# SquidPage.net
KiCad netlist of a schematic drawn in Altium Designer
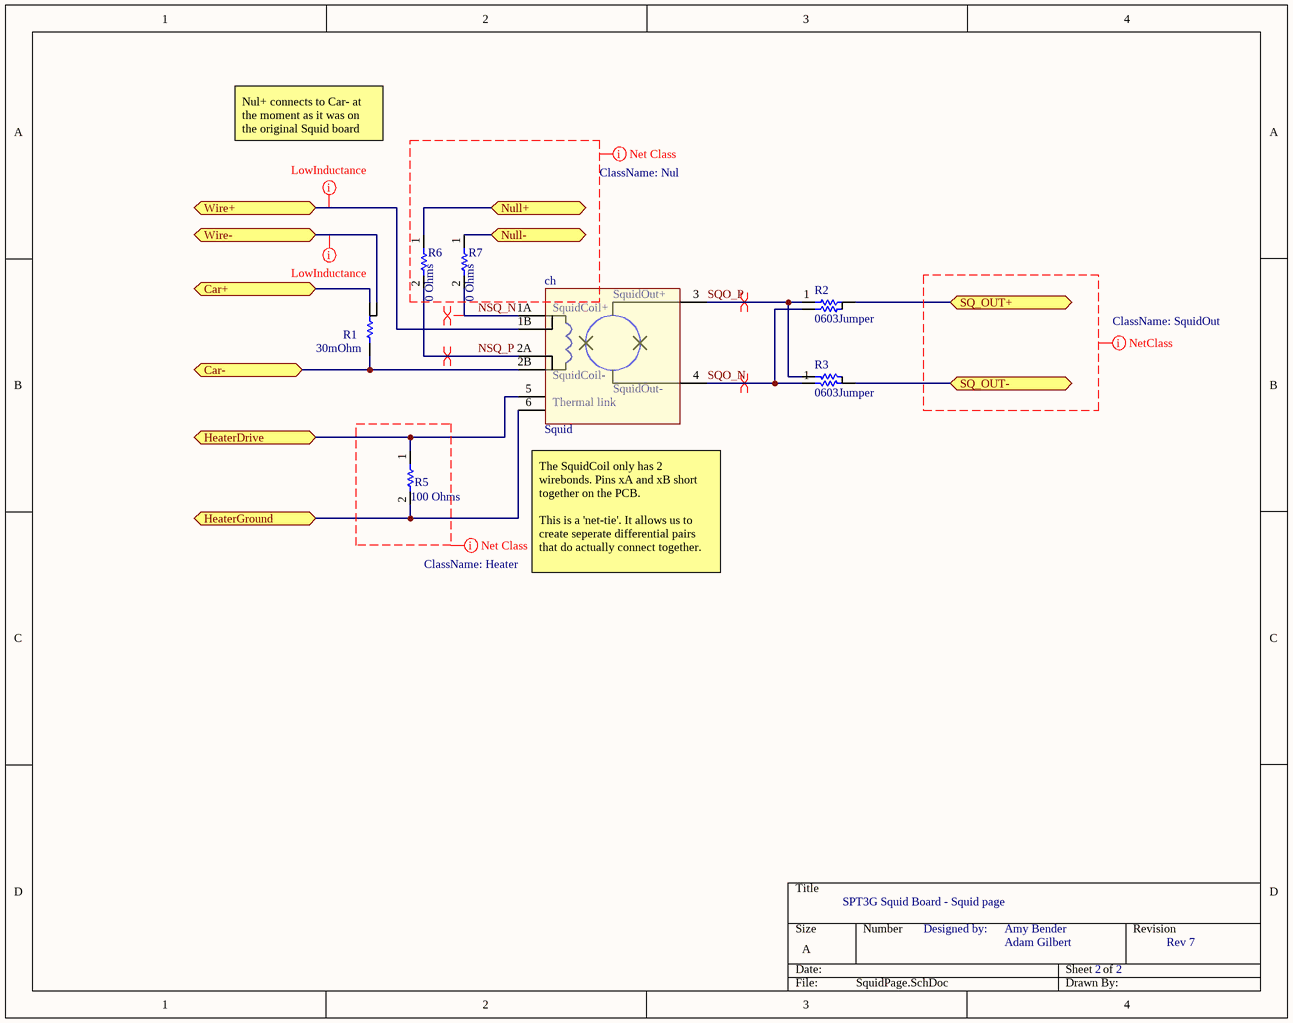
[diagram p0: SquidPage.SchDoc]

(export (version "E")
  (design (tool "Eeschema 10.0.6"))
  (components
    (comp (ref "ch") (value "Squid") (footprint "Squid2") (libsource (lib "SPT3G_LCBoard") (part "Squid")))
    (comp (ref "R1")
      (value "30mOhm")
      (footprint "0805NetTie")
      (description "Resistor 30mOhm")
      (fields (field (name "Comment") "ResBias"))
      (libsource (lib "SPT3G_LCBoard") (part "ResBias"))
    )
    (comp (ref "R2")
      (value "0603Jumper")
      (footprint "0603-jumper")
      (description "RES 0 OHM 1/10W 1% 0603 SMD")
      (libsource (lib "SPT3G_LCBoard") (part "0603Jumper"))
    )
    (comp (ref "R3")
      (value "0603Jumper")
      (footprint "0603-jumper")
      (description "RES 0 OHM 1/10W 1% 0603 SMD")
      (libsource (lib "SPT3G_LCBoard") (part "0603Jumper"))
    )
    (comp (ref "R5")
      (value "100 Ohms")
      (footprint "0603-NoSilk")
      (description "Resistor")
      (fields (field (name "Comment") "ResSquidBoard"))
      (libsource (lib "SPT3G_LCBoard") (part "ResSquidBoard"))
    )
    (comp (ref "R6")
      (value "0 Ohms")
      (footprint "0603")
      (description "Resistor")
      (fields (field (name "Comment") "ResSquidBoard"))
      (libsource (lib "SPT3G_LCBoard") (part "ResSquidBoard"))
    )
    (comp (ref "R7")
      (value "0 Ohms")
      (footprint "0603")
      (description "Resistor")
      (fields (field (name "Comment") "ResSquidBoard"))
      (libsource (lib "SPT3G_LCBoard") (part "ResSquidBoard"))
    )
  )
  (nets
    (net (code "1") (name "/Car+") (class "Default")
      (node (ref "R1") (pin "2A") (pinfunction "2_2A") (pintype "passive"))
    )
    (net (code "2") (name "/Car-") (class "Default")
      (node (ref "R1") (pin "1") (pinfunction "1_1") (pintype "passive"))
      (node (ref "ch") (pin "2B") (pinfunction "SquidCoil-_2B") (pintype "passive"))
    )
    (net (code "3") (name "/HeaterDrive") (class "Default")
      (node (ref "R5") (pin "1") (pinfunction "1_1") (pintype "passive"))
      (node (ref "ch") (pin "5") (pinfunction "Heater_5") (pintype "passive"))
    )
    (net (code "4") (name "/HeaterGround") (class "Default")
      (node (ref "R5") (pin "2") (pinfunction "2_2") (pintype "passive"))
      (node (ref "ch") (pin "6") (pinfunction "HeaterGnd_6") (pintype "passive"))
    )
    (net (code "5") (name "/NSQ_N") (class "Default")
      (node (ref "R7") (pin "2") (pinfunction "2_2") (pintype "passive"))
      (node (ref "ch") (pin "1A") (pinfunction "SquidCoil+_1A") (pintype "passive"))
    )
    (net (code "6") (name "/NSQ_P") (class "Default")
      (node (ref "R6") (pin "2") (pinfunction "2_2") (pintype "passive"))
      (node (ref "ch") (pin "2A") (pinfunction "SquidCoil-_2A") (pintype "passive"))
    )
    (net (code "7") (name "/Null+") (class "Default")
      (node (ref "R6") (pin "1") (pinfunction "1_1") (pintype "passive"))
    )
    (net (code "8") (name "/Null-") (class "Default")
      (node (ref "R7") (pin "1") (pinfunction "1_1") (pintype "passive"))
    )
    (net (code "9") (name "/SQO_N") (class "Default")
      (node (ref "R2") (pin "3") (pinfunction "3_3") (pintype "passive"))
      (node (ref "R3") (pin "1") (pinfunction "1_1") (pintype "passive"))
      (node (ref "ch") (pin "4") (pinfunction "SQUID-_4") (pintype "passive"))
    )
    (net (code "10") (name "/SQO_P") (class "Default")
      (node (ref "R2") (pin "1") (pinfunction "1_1") (pintype "passive"))
      (node (ref "R3") (pin "3") (pinfunction "3_3") (pintype "passive"))
      (node (ref "ch") (pin "3") (pinfunction "SQUID+_3") (pintype "passive"))
    )
    (net (code "11") (name "/SQ_OUT+") (class "Default")
      (node (ref "R2") (pin "2") (pinfunction "2_2") (pintype "passive"))
    )
    (net (code "12") (name "/SQ_OUT-") (class "Default")
      (node (ref "R3") (pin "2") (pinfunction "2_2") (pintype "passive"))
    )
    (net (code "13") (name "/Wire+") (class "Default")
      (node (ref "ch") (pin "1B") (pinfunction "SquidCoil+_1B") (pintype "passive"))
    )
    (net (code "14") (name "/Wire-") (class "Default")
      (node (ref "R1") (pin "2B") (pinfunction "2_2B") (pintype "passive"))
    )
  )
)
